# Sch_ALICE.net
KiCad netlist of a schematic drawn in Altium Designer
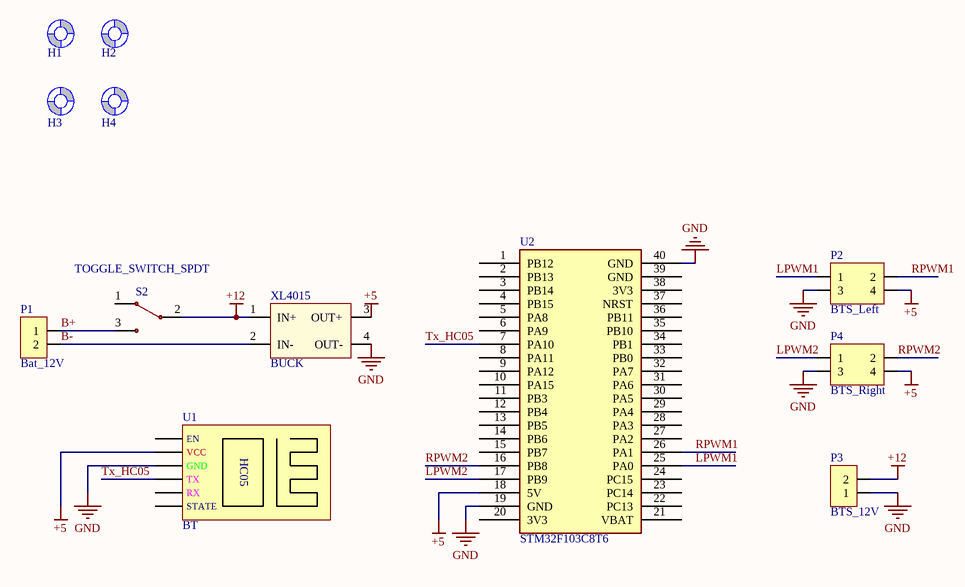
[diagram p0: Sch_ALICE.SchDoc]

(export (version "E")
  (design (tool "Eeschema 10.0.6"))
  (components
    (comp (ref "H1")
      (value "Screw Hole")
      (footprint "SCREW/3.0/6.0")
      (libsource (lib "chipfc_libs") (part "Screw Hole"))
    )
    (comp (ref "H2")
      (value "Screw Hole")
      (footprint "SCREW/3.0/6.0")
      (libsource (lib "chipfc_libs") (part "Screw Hole"))
    )
    (comp (ref "H3")
      (value "Screw Hole")
      (footprint "SCREW/3.0/6.0")
      (libsource (lib "chipfc_libs") (part "Screw Hole"))
    )
    (comp (ref "H4")
      (value "Screw Hole")
      (footprint "SCREW/3.0/6.0")
      (libsource (lib "chipfc_libs") (part "Screw Hole"))
    )
    (comp (ref "P1")
      (value "Bat_12V")
      (footprint "HDR/Terminal/2/5mm")
      (description "Header, 2-Pin")
      (libsource (lib "connectors") (part "Header 2"))
    )
    (comp (ref "P2")
      (value "BTS_Left")
      (footprint "HDR/Header/4/DL")
      (description "Header, 2-Pin, Dual row")
      (libsource (lib "connectors") (part "Header 2X2"))
    )
    (comp (ref "P3")
      (value "BTS_12V")
      (footprint "HDR/Terminal/2/5mm")
      (description "Header, 2-Pin")
      (libsource (lib "") (part "Header 2_1"))
    )
    (comp (ref "P4")
      (value "BTS_Right")
      (footprint "HDR/Header/4/DL")
      (description "Header, 2-Pin, Dual row")
      (libsource (lib "connectors") (part "Header 2X2"))
    )
    (comp (ref "S2")
      (value "TOGGLE_SWITCH_SPDT")
      (footprint "TOGGLE_SWITCH_SPDT")
      (description "Toggle Switch SPDT, 125V AC, 6A, 33x13x7mm.")
      (libsource (lib "Buttons & Switches") (part "TOGGLE_SWITCH_SPDT"))
    )
    (comp (ref "U1")
      (value "BT")
      (footprint "HC05")
      (description "Bluetooth HC05 Module")
      (libsource (lib "Schlib1") (part "HC05"))
    )
    (comp (ref "U2")
      (value "STM32F103C8T6")
      (footprint "Stm32 BluePill")
      (description "Designed By @Alixahedi")
      (libsource (lib "Stm32 Blue Pill") (part "BluePill"))
    )
    (comp (ref "XL4015")
      (value "BUCK")
      (footprint "PCBComponent_1")
      (libsource (lib "Schlib1") (part "BUCK"))
    )
  )
  (nets
    (net (code "1") (name "+5") (class "Default")
      (node (ref "P2") (pin "4") (pinfunction "4_4") (pintype "passive"))
      (node (ref "P4") (pin "4") (pinfunction "4_4") (pintype "passive"))
      (node (ref "U1") (pin "2") (pintype "passive"))
      (node (ref "U2") (pin "18") (pinfunction "5V_18") (pintype "passive"))
      (node (ref "XL4015") (pin "3") (pinfunction "OUT+_3") (pintype "passive"))
    )
    (net (code "2") (name "+12") (class "Default")
      (node (ref "P3") (pin "2") (pinfunction "2_2") (pintype "passive"))
      (node (ref "S2") (pin "2") (pinfunction "2_2") (pintype "passive"))
      (node (ref "XL4015") (pin "1") (pinfunction "IN+_1") (pintype "passive"))
    )
    (net (code "3") (name "/B+") (class "Default")
      (node (ref "P1") (pin "1") (pinfunction "1_1") (pintype "passive"))
      (node (ref "S2") (pin "3") (pinfunction "3_3") (pintype "passive"))
    )
    (net (code "4") (name "/B-") (class "Default")
      (node (ref "P1") (pin "2") (pinfunction "2_2") (pintype "passive"))
      (node (ref "XL4015") (pin "2") (pinfunction "IN-_2") (pintype "passive"))
    )
    (net (code "5") (name "/LPWM1") (class "Default")
      (node (ref "P2") (pin "1") (pinfunction "1_1") (pintype "passive"))
      (node (ref "U2") (pin "25") (pinfunction "PA0_25") (pintype "passive"))
    )
    (net (code "6") (name "/LPWM2") (class "Default")
      (node (ref "P4") (pin "1") (pinfunction "1_1") (pintype "passive"))
      (node (ref "U2") (pin "17") (pinfunction "PB9_17") (pintype "passive"))
    )
    (net (code "7") (name "/RPWM1") (class "Default")
      (node (ref "P2") (pin "2") (pinfunction "2_2") (pintype "passive"))
      (node (ref "U2") (pin "26") (pinfunction "PA1_26") (pintype "passive"))
    )
    (net (code "8") (name "/RPWM2") (class "Default")
      (node (ref "P4") (pin "2") (pinfunction "2_2") (pintype "passive"))
      (node (ref "U2") (pin "16") (pinfunction "PB8_16") (pintype "passive"))
    )
    (net (code "9") (name "/Tx_HC05") (class "Default")
      (node (ref "U1") (pin "4") (pintype "passive"))
      (node (ref "U2") (pin "7") (pinfunction "PA10_7") (pintype "passive"))
    )
    (net (code "10") (name "GND") (class "Default")
      (node (ref "P2") (pin "3") (pinfunction "3_3") (pintype "passive"))
      (node (ref "P3") (pin "1") (pinfunction "1_1") (pintype "passive"))
      (node (ref "P4") (pin "3") (pinfunction "3_3") (pintype "passive"))
      (node (ref "U1") (pin "3") (pintype "passive"))
      (node (ref "U2") (pin "19") (pinfunction "GND_19") (pintype "passive"))
      (node (ref "U2") (pin "40") (pinfunction "GND_40") (pintype "passive"))
      (node (ref "XL4015") (pin "4") (pinfunction "OUT-_4") (pintype "passive"))
    )
    (net (code "11") (name "unconnected-(H1-Screw-Pad1)") (class "Default")
      (node (ref "H1") (pin "1") (pinfunction "Screw_1") (pintype "passive"))
    )
    (net (code "12") (name "unconnected-(H2-Screw-Pad1)") (class "Default")
      (node (ref "H2") (pin "1") (pinfunction "Screw_1") (pintype "passive"))
    )
    (net (code "13") (name "unconnected-(H3-Screw-Pad1)") (class "Default")
      (node (ref "H3") (pin "1") (pinfunction "Screw_1") (pintype "passive"))
    )
    (net (code "14") (name "unconnected-(H4-Screw-Pad1)") (class "Default")
      (node (ref "H4") (pin "1") (pinfunction "Screw_1") (pintype "passive"))
    )
    (net (code "15") (name "unconnected-(S2-Pad1)") (class "Default")
      (node (ref "S2") (pin "1") (pinfunction "1_1") (pintype "passive"))
    )
    (net (code "16") (name "unconnected-(U1-Pad1)") (class "Default")
      (node (ref "U1") (pin "1") (pintype "passive"))
    )
    (net (code "17") (name "unconnected-(U1-Pad5)") (class "Default")
      (node (ref "U1") (pin "5") (pintype "passive"))
    )
    (net (code "18") (name "unconnected-(U1-Pad6)") (class "Default")
      (node (ref "U1") (pin "6") (pintype "passive"))
    )
    (net (code "19") (name "unconnected-(U2-3V3-Pad20)") (class "Default")
      (node (ref "U2") (pin "20") (pinfunction "3V3_20") (pintype "passive"))
    )
    (net (code "20") (name "unconnected-(U2-3V3-Pad38)") (class "Default")
      (node (ref "U2") (pin "38") (pinfunction "3V3_38") (pintype "passive"))
    )
    (net (code "21") (name "unconnected-(U2-GND-Pad39)") (class "Default")
      (node (ref "U2") (pin "39") (pinfunction "GND_39") (pintype "passive"))
    )
    (net (code "22") (name "unconnected-(U2-NRST-Pad37)") (class "Default")
      (node (ref "U2") (pin "37") (pinfunction "NRST_37") (pintype "passive"))
    )
    (net (code "23") (name "unconnected-(U2-PA2-Pad27)") (class "Default")
      (node (ref "U2") (pin "27") (pinfunction "PA2_27") (pintype "passive"))
    )
    (net (code "24") (name "unconnected-(U2-PA3-Pad28)") (class "Default")
      (node (ref "U2") (pin "28") (pinfunction "PA3_28") (pintype "passive"))
    )
    (net (code "25") (name "unconnected-(U2-PA4-Pad29)") (class "Default")
      (node (ref "U2") (pin "29") (pinfunction "PA4_29") (pintype "passive"))
    )
    (net (code "26") (name "unconnected-(U2-PA5-Pad30)") (class "Default")
      (node (ref "U2") (pin "30") (pinfunction "PA5_30") (pintype "passive"))
    )
    (net (code "27") (name "unconnected-(U2-PA6-Pad31)") (class "Default")
      (node (ref "U2") (pin "31") (pinfunction "PA6_31") (pintype "passive"))
    )
    (net (code "28") (name "unconnected-(U2-PA7-Pad32)") (class "Default")
      (node (ref "U2") (pin "32") (pinfunction "PA7_32") (pintype "passive"))
    )
    (net (code "29") (name "unconnected-(U2-PA8-Pad5)") (class "Default")
      (node (ref "U2") (pin "5") (pinfunction "PA8_5") (pintype "passive"))
    )
    (net (code "30") (name "unconnected-(U2-PA9-Pad6)") (class "Default")
      (node (ref "U2") (pin "6") (pinfunction "PA9_6") (pintype "passive"))
    )
    (net (code "31") (name "unconnected-(U2-PA11-Pad8)") (class "Default")
      (node (ref "U2") (pin "8") (pinfunction "PA11_8") (pintype "passive"))
    )
    (net (code "32") (name "unconnected-(U2-PA12-Pad9)") (class "Default")
      (node (ref "U2") (pin "9") (pinfunction "PA12_9") (pintype "passive"))
    )
    (net (code "33") (name "unconnected-(U2-PA15-Pad10)") (class "Default")
      (node (ref "U2") (pin "10") (pinfunction "PA15_10") (pintype "passive"))
    )
    (net (code "34") (name "unconnected-(U2-PB0-Pad33)") (class "Default")
      (node (ref "U2") (pin "33") (pinfunction "PB0_33") (pintype "passive"))
    )
    (net (code "35") (name "unconnected-(U2-PB1-Pad34)") (class "Default")
      (node (ref "U2") (pin "34") (pinfunction "PB1_34") (pintype "passive"))
    )
    (net (code "36") (name "unconnected-(U2-PB3-Pad11)") (class "Default")
      (node (ref "U2") (pin "11") (pinfunction "PB3_11") (pintype "passive"))
    )
    (net (code "37") (name "unconnected-(U2-PB4-Pad12)") (class "Default")
      (node (ref "U2") (pin "12") (pinfunction "PB4_12") (pintype "passive"))
    )
    (net (code "38") (name "unconnected-(U2-PB5-Pad13)") (class "Default")
      (node (ref "U2") (pin "13") (pinfunction "PB5_13") (pintype "passive"))
    )
    (net (code "39") (name "unconnected-(U2-PB6-Pad14)") (class "Default")
      (node (ref "U2") (pin "14") (pinfunction "PB6_14") (pintype "passive"))
    )
    (net (code "40") (name "unconnected-(U2-PB7-Pad15)") (class "Default")
      (node (ref "U2") (pin "15") (pinfunction "PB7_15") (pintype "passive"))
    )
    (net (code "41") (name "unconnected-(U2-PB10-Pad35)") (class "Default")
      (node (ref "U2") (pin "35") (pinfunction "PB10_35") (pintype "passive"))
    )
    (net (code "42") (name "unconnected-(U2-PB11-Pad36)") (class "Default")
      (node (ref "U2") (pin "36") (pinfunction "PB11_36") (pintype "passive"))
    )
    (net (code "43") (name "unconnected-(U2-PB12-Pad1)") (class "Default")
      (node (ref "U2") (pin "1") (pinfunction "PB12_1") (pintype "passive"))
    )
    (net (code "44") (name "unconnected-(U2-PB13-Pad2)") (class "Default")
      (node (ref "U2") (pin "2") (pinfunction "PB13_2") (pintype "passive"))
    )
    (net (code "45") (name "unconnected-(U2-PB14-Pad3)") (class "Default")
      (node (ref "U2") (pin "3") (pinfunction "PB14_3") (pintype "passive"))
    )
    (net (code "46") (name "unconnected-(U2-PB15-Pad4)") (class "Default")
      (node (ref "U2") (pin "4") (pinfunction "PB15_4") (pintype "passive"))
    )
    (net (code "47") (name "unconnected-(U2-PC13-Pad22)") (class "Default")
      (node (ref "U2") (pin "22") (pinfunction "PC13_22") (pintype "passive"))
    )
    (net (code "48") (name "unconnected-(U2-PC14-Pad23)") (class "Default")
      (node (ref "U2") (pin "23") (pinfunction "PC14_23") (pintype "passive"))
    )
    (net (code "49") (name "unconnected-(U2-PC15-Pad24)") (class "Default")
      (node (ref "U2") (pin "24") (pinfunction "PC15_24") (pintype "passive"))
    )
    (net (code "50") (name "unconnected-(U2-VBAT-Pad21)") (class "Default")
      (node (ref "U2") (pin "21") (pinfunction "VBAT_21") (pintype "passive"))
    )
  )
)
